# ad7249.net
KiCad netlist of a schematic drawn in EAGLE
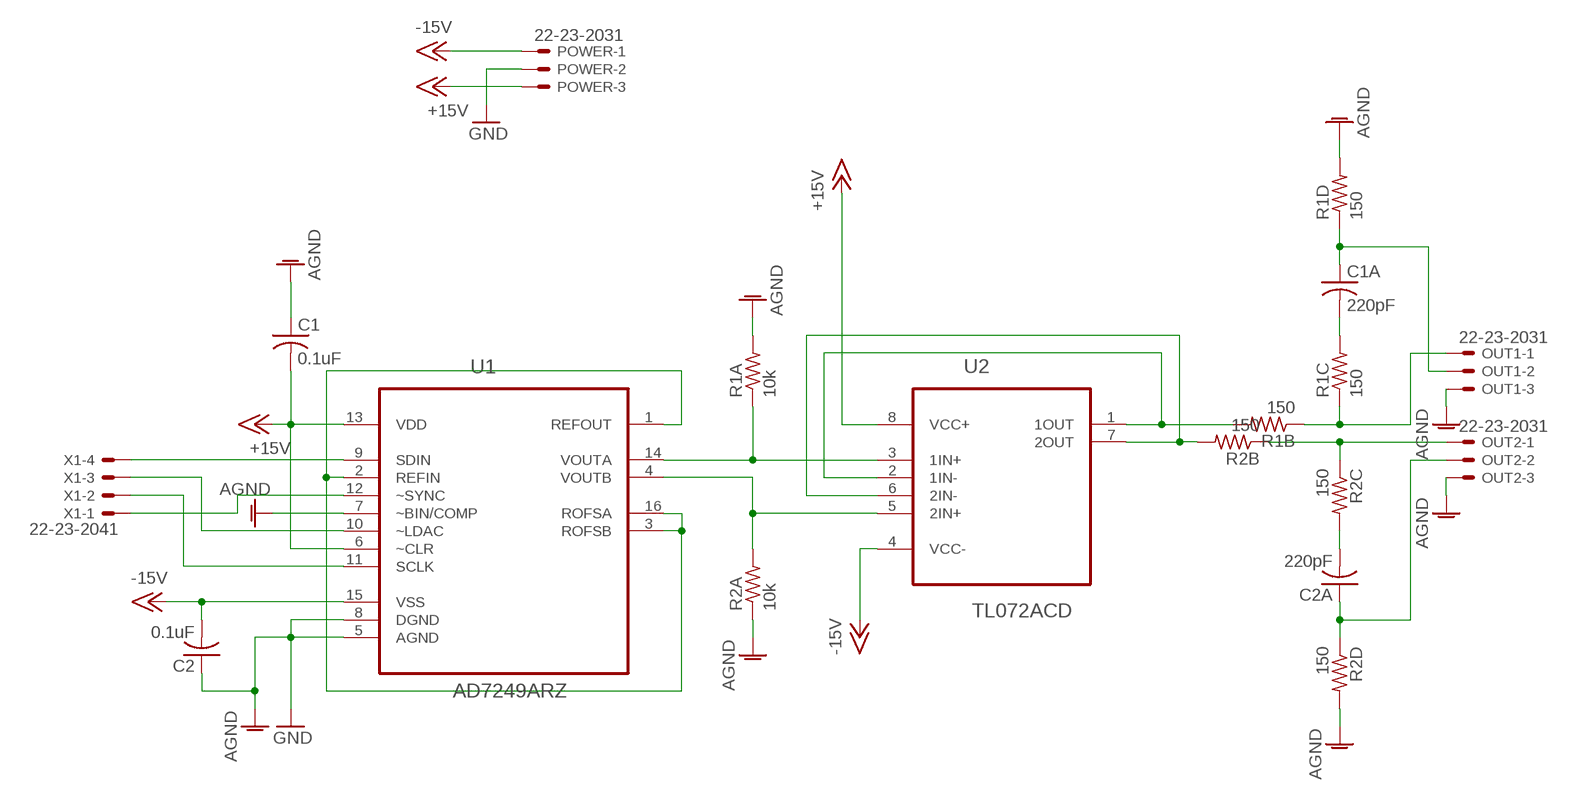
[diagram p0: schematic, sheet 1]

(export (version "E")
  (design (tool "Eeschema 10.0.6"))
  (components
    (comp (ref "C1")
      (value "0.1uF")
      (footprint "eagle-import:C1206")
      (libsource (lib "eagle-import") (part "C-USC1206"))
    )
    (comp (ref "C1A")
      (value "220pF")
      (footprint "eagle-import:C1206")
      (libsource (lib "eagle-import") (part "C-USC1206"))
    )
    (comp (ref "C2")
      (value "0.1uF")
      (footprint "eagle-import:C1206")
      (libsource (lib "eagle-import") (part "C-USC1206"))
    )
    (comp (ref "C2A")
      (value "220pF")
      (footprint "eagle-import:C1206")
      (libsource (lib "eagle-import") (part "C-USC1206"))
    )
    (comp (ref "OUT1")
      (value "22-23-2031")
      (footprint "eagle-import:22-23-2031")
      (fields (field (name "MF") "MOLEX"))
      (libsource (lib "eagle-import") (part "22-23-2031"))
    )
    (comp (ref "OUT2")
      (value "22-23-2031")
      (footprint "eagle-import:22-23-2031")
      (fields (field (name "MF") "MOLEX"))
      (libsource (lib "eagle-import") (part "22-23-2031"))
    )
    (comp (ref "POWER")
      (value "22-23-2031")
      (footprint "eagle-import:22-23-2031")
      (fields
        (field (name "MF") "MOLEX")
        (field (name "MF_1") "MOLEX")
        (field (name "MPN") "22-23-2031")
        (field (name "OC_FARNELL") "1462950")
        (field (name "OC_NEWARK") "30C0862")
      )
      (libsource (lib "eagle-import") (part "22-23-2031"))
    )
    (comp (ref "R1A")
      (value "10k")
      (footprint "eagle-import:R1206")
      (libsource (lib "eagle-import") (part "R-US_R1206"))
    )
    (comp (ref "R1B")
      (value "150")
      (footprint "eagle-import:R1206")
      (libsource (lib "eagle-import") (part "R-US_R1206"))
    )
    (comp (ref "R1C")
      (value "150")
      (footprint "eagle-import:R1206")
      (libsource (lib "eagle-import") (part "R-US_R1206"))
    )
    (comp (ref "R1D")
      (value "150")
      (footprint "eagle-import:R1206")
      (libsource (lib "eagle-import") (part "R-US_R1206"))
    )
    (comp (ref "R2A")
      (value "10k")
      (footprint "eagle-import:R1206")
      (libsource (lib "eagle-import") (part "R-US_R1206"))
    )
    (comp (ref "R2B")
      (value "150")
      (footprint "eagle-import:R1206")
      (libsource (lib "eagle-import") (part "R-US_R1206"))
    )
    (comp (ref "R2C")
      (value "150")
      (footprint "eagle-import:R1206")
      (libsource (lib "eagle-import") (part "R-US_R1206"))
    )
    (comp (ref "R2D")
      (value "150")
      (footprint "eagle-import:R1206")
      (libsource (lib "eagle-import") (part "R-US_R1206"))
    )
    (comp (ref "U1")
      (value "AD7249ARZ")
      (footprint "eagle-import:SOIC127P1042X272-16N")
      (libsource (lib "eagle-import") (part "AD7249ARZ"))
    )
    (comp (ref "U2")
      (value "TL072ACD")
      (footprint "eagle-import:SOIC127P600X175-8N")
      (libsource (lib "eagle-import") (part "TL072ACD"))
    )
    (comp (ref "X1")
      (value "22-23-2041")
      (footprint "eagle-import:22-23-2041")
      (fields (field (name "MF") "MOLEX"))
      (libsource (lib "eagle-import") (part "22-23-2041"))
    )
  )
  (nets
    (net (code "1") (name "+15V") (class "Default")
      (node (ref "C1") (pin "2") (pinfunction "2_2") (pintype "passive"))
      (node (ref "POWER") (pin "3") (pinfunction "S_3") (pintype "passive"))
      (node (ref "U1") (pin "13") (pinfunction "VDD_13") (pintype "power_in"))
      (node (ref "U1") (pin "6") (pinfunction "~{CLR}_6") (pintype "input"))
      (node (ref "U2") (pin "8") (pinfunction "VCC+_8") (pintype "power_in"))
    )
    (net (code "2") (name "-15V") (class "Default")
      (node (ref "C2") (pin "2") (pinfunction "2_2") (pintype "passive"))
      (node (ref "POWER") (pin "1") (pinfunction "S_1") (pintype "passive"))
      (node (ref "U1") (pin "15") (pinfunction "VSS_15") (pintype "power_in"))
      (node (ref "U2") (pin "4") (pinfunction "VCC-_4") (pintype "power_in"))
    )
    (net (code "3") (name "AGND") (class "Default")
      (node (ref "C1") (pin "1") (pinfunction "1_1") (pintype "passive"))
      (node (ref "C2") (pin "1") (pinfunction "1_1") (pintype "passive"))
      (node (ref "OUT1") (pin "3") (pinfunction "S_3") (pintype "passive"))
      (node (ref "OUT2") (pin "3") (pinfunction "S_3") (pintype "passive"))
      (node (ref "POWER") (pin "2") (pinfunction "S_2") (pintype "passive"))
      (node (ref "R1A") (pin "2") (pinfunction "2_2") (pintype "passive"))
      (node (ref "R1D") (pin "2") (pinfunction "2_2") (pintype "passive"))
      (node (ref "R2A") (pin "1") (pinfunction "1_1") (pintype "passive"))
      (node (ref "R2D") (pin "2") (pinfunction "2_2") (pintype "passive"))
      (node (ref "U1") (pin "5") (pinfunction "AGND_5") (pintype "passive"))
      (node (ref "U1") (pin "7") (pinfunction "~{BIN/COMP}_7") (pintype "input"))
      (node (ref "U1") (pin "8") (pinfunction "DGND_8") (pintype "passive"))
    )
    (net (code "4") (name "Net-(C1A-Pad2)") (class "Default")
      (node (ref "C1A") (pin "2") (pinfunction "2_2") (pintype "passive"))
      (node (ref "R1C") (pin "2") (pinfunction "2_2") (pintype "passive"))
    )
    (net (code "5") (name "Net-(C2A-Pad2)") (class "Default")
      (node (ref "C2A") (pin "2") (pinfunction "2_2") (pintype "passive"))
      (node (ref "R2C") (pin "2") (pinfunction "2_2") (pintype "passive"))
    )
    (net (code "6") (name "Net-(OUT1A-S)") (class "Default")
      (node (ref "OUT1") (pin "1") (pinfunction "S_1") (pintype "passive"))
      (node (ref "R1B") (pin "1") (pinfunction "1_1") (pintype "passive"))
      (node (ref "R1C") (pin "1") (pinfunction "1_1") (pintype "passive"))
    )
    (net (code "7") (name "Net-(OUT1B-S)") (class "Default")
      (node (ref "C1A") (pin "1") (pinfunction "1_1") (pintype "passive"))
      (node (ref "OUT1") (pin "2") (pinfunction "S_2") (pintype "passive"))
      (node (ref "R1D") (pin "1") (pinfunction "1_1") (pintype "passive"))
    )
    (net (code "8") (name "Net-(OUT2A-S)") (class "Default")
      (node (ref "OUT2") (pin "1") (pinfunction "S_1") (pintype "passive"))
      (node (ref "R2B") (pin "1") (pinfunction "1_1") (pintype "passive"))
      (node (ref "R2C") (pin "1") (pinfunction "1_1") (pintype "passive"))
    )
    (net (code "9") (name "Net-(OUT2B-S)") (class "Default")
      (node (ref "C2A") (pin "1") (pinfunction "1_1") (pintype "passive"))
      (node (ref "OUT2") (pin "2") (pinfunction "S_2") (pintype "passive"))
      (node (ref "R2D") (pin "1") (pinfunction "1_1") (pintype "passive"))
    )
    (net (code "10") (name "Net-(U1-REFIN)") (class "Default")
      (node (ref "U1") (pin "1") (pinfunction "REFOUT_1") (pintype "output"))
      (node (ref "U1") (pin "16") (pinfunction "ROFSA_16") (pintype "output"))
      (node (ref "U1") (pin "2") (pinfunction "REFIN_2") (pintype "input"))
      (node (ref "U1") (pin "3") (pinfunction "ROFSB_3") (pintype "output"))
    )
    (net (code "11") (name "Net-(U1-SCLK)") (class "Default")
      (node (ref "U1") (pin "11") (pinfunction "SCLK_11") (pintype "input"))
      (node (ref "X1") (pin "2") (pinfunction "S_2") (pintype "passive"))
    )
    (net (code "12") (name "Net-(U1-SDIN)") (class "Default")
      (node (ref "U1") (pin "9") (pinfunction "SDIN_9") (pintype "input"))
      (node (ref "X1") (pin "4") (pinfunction "S_4") (pintype "passive"))
    )
    (net (code "13") (name "Net-(U1-VOUTA)") (class "Default")
      (node (ref "R1A") (pin "1") (pinfunction "1_1") (pintype "passive"))
      (node (ref "U1") (pin "14") (pinfunction "VOUTA_14") (pintype "output"))
      (node (ref "U2") (pin "3") (pinfunction "1IN+_3") (pintype "input"))
    )
    (net (code "14") (name "Net-(U1-VOUTB)") (class "Default")
      (node (ref "R2A") (pin "2") (pinfunction "2_2") (pintype "passive"))
      (node (ref "U1") (pin "4") (pinfunction "VOUTB_4") (pintype "output"))
      (node (ref "U2") (pin "5") (pinfunction "2IN+_5") (pintype "input"))
    )
    (net (code "15") (name "Net-(U1-~{LDAC})") (class "Default")
      (node (ref "U1") (pin "10") (pinfunction "~{LDAC}_10") (pintype "input"))
      (node (ref "X1") (pin "3") (pinfunction "S_3") (pintype "passive"))
    )
    (net (code "16") (name "Net-(U1-~{SYNC})") (class "Default")
      (node (ref "U1") (pin "12") (pinfunction "~{SYNC}_12") (pintype "input"))
      (node (ref "X1") (pin "1") (pinfunction "S_1") (pintype "passive"))
    )
    (net (code "17") (name "Net-(U2-1IN-)") (class "Default")
      (node (ref "R1B") (pin "2") (pinfunction "2_2") (pintype "passive"))
      (node (ref "U2") (pin "1") (pinfunction "1OUT_1") (pintype "output"))
      (node (ref "U2") (pin "2") (pinfunction "1IN-_2") (pintype "input"))
    )
    (net (code "18") (name "Net-(U2-2IN-)") (class "Default")
      (node (ref "R2B") (pin "2") (pinfunction "2_2") (pintype "passive"))
      (node (ref "U2") (pin "6") (pinfunction "2IN-_6") (pintype "input"))
      (node (ref "U2") (pin "7") (pinfunction "2OUT_7") (pintype "output"))
    )
  )
)
